# schemat1.net
KiCad netlist of a schematic drawn in EAGLE
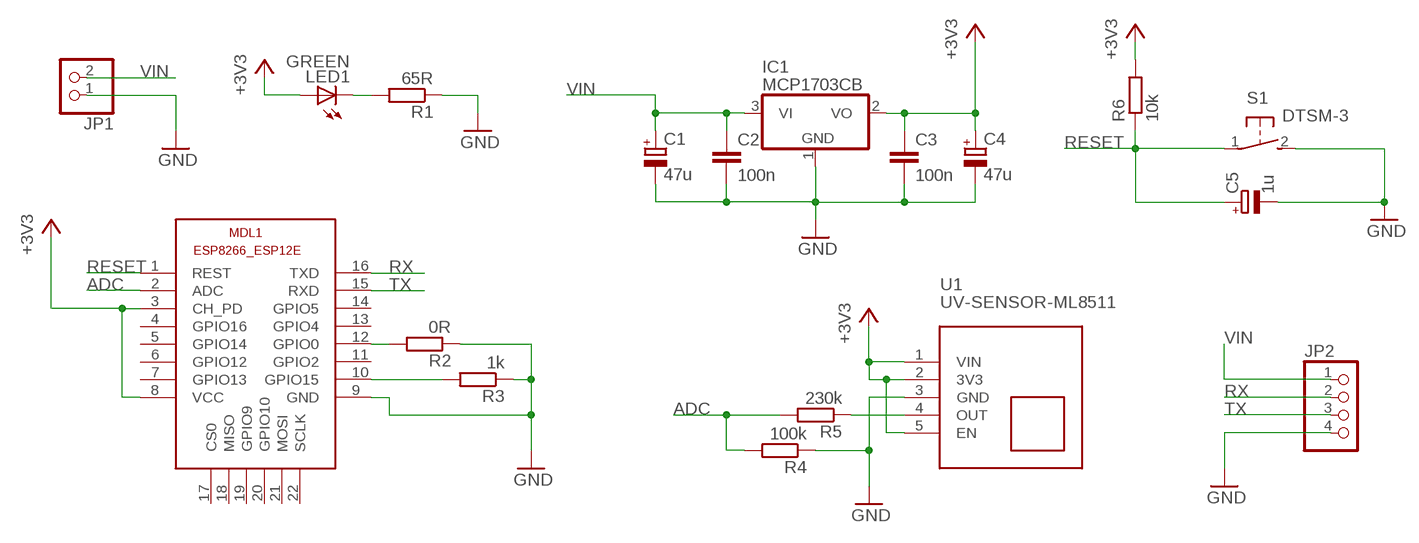
[diagram p0: schematic, sheet 1]

(export (version "E")
  (design (tool "Eeschema 10.0.6"))
  (components
    (comp (ref "C1")
      (value "47u")
      (footprint "eagle-import:CT3528")
      (libsource (lib "eagle-import") (part "CPOL-EUCT3528"))
    )
    (comp (ref "C2")
      (value "100n")
      (footprint "eagle-import:C0805")
      (libsource (lib "eagle-import") (part "C-EUC0805"))
    )
    (comp (ref "C3")
      (value "100n")
      (footprint "eagle-import:C0805")
      (libsource (lib "eagle-import") (part "C-EUC0805"))
    )
    (comp (ref "C4")
      (value "47u")
      (footprint "eagle-import:CT3528")
      (libsource (lib "eagle-import") (part "CPOL-EUCT3528"))
    )
    (comp (ref "C5")
      (value "1u")
      (footprint "eagle-import:CT3216")
      (libsource (lib "eagle-import") (part "CPOL-EUCT3216"))
    )
    (comp (ref "IC1")
      (value "MCP1703CB")
      (footprint "eagle-import:SOT23")
      (libsource (lib "eagle-import") (part "MCP1703CB"))
    )
    (comp (ref "JP1")
      (value "PINHD-1X2")
      (footprint "eagle-import:1X02")
      (libsource (lib "eagle-import") (part "PINHD-1X2"))
    )
    (comp (ref "JP2")
      (value "PINHD-1X4/90")
      (footprint "eagle-import:1X04_90")
      (libsource (lib "eagle-import") (part "PINHD-1X4/90"))
    )
    (comp (ref "LED1")
      (value "GREEN")
      (footprint "eagle-import:LED_1206")
      (libsource (lib "eagle-import") (part "LED_E"))
    )
    (comp (ref "MDL1")
      (value "ESP8266-12EESP8266-ESP12E")
      (footprint "eagle-import:ESP8266-ESP12E")
      (libsource (lib "eagle-import") (part "ESP8266-12EESP8266-ESP12E"))
    )
    (comp (ref "R1")
      (value "65R")
      (footprint "eagle-import:R0805")
      (libsource (lib "eagle-import") (part "R-EU_R0805"))
    )
    (comp (ref "R2")
      (value "0R")
      (footprint "eagle-import:R0805")
      (libsource (lib "eagle-import") (part "R-EU_R0805"))
    )
    (comp (ref "R3")
      (value "1k")
      (footprint "eagle-import:R0805")
      (libsource (lib "eagle-import") (part "R-EU_R0805"))
    )
    (comp (ref "R4")
      (value "100k")
      (footprint "eagle-import:R0805")
      (libsource (lib "eagle-import") (part "R-EU_R0805"))
    )
    (comp (ref "R5")
      (value "230k")
      (footprint "eagle-import:R0805")
      (libsource (lib "eagle-import") (part "R-EU_R0805"))
    )
    (comp (ref "R6")
      (value "10k")
      (footprint "eagle-import:R0805")
      (libsource (lib "eagle-import") (part "R-EU_R0805"))
    )
    (comp (ref "S1")
      (value "DTSM-3")
      (footprint "eagle-import:DTSM-3")
      (libsource (lib "eagle-import") (part "DTSM-3"))
    )
    (comp (ref "U1")
      (value "UV-SENSOR-ML8511")
      (footprint "eagle-import:UV-SENSOR-ML8511")
      (libsource (lib "eagle-import") (part "UV-SENSOR-ML8511"))
    )
  )
  (nets
    (net (code "1") (name "+3V3") (class "Default")
      (node (ref "C3") (pin "1") (pinfunction "1_1") (pintype "passive"))
      (node (ref "C4") (pin "+") (pinfunction "+_+") (pintype "passive"))
      (node (ref "IC1") (pin "2") (pinfunction "VO_2") (pintype "passive"))
      (node (ref "LED1") (pin "A") (pinfunction "A_A") (pintype "passive"))
      (node (ref "MDL1") (pin "3") (pinfunction "CH_PD_3") (pintype "bidirectional"))
      (node (ref "MDL1") (pin "8") (pinfunction "VCC_8") (pintype "bidirectional"))
      (node (ref "R6") (pin "2") (pinfunction "2_2") (pintype "passive"))
      (node (ref "U1") (pin "1") (pinfunction "VIN_1") (pintype "power_in"))
      (node (ref "U1") (pin "2") (pinfunction "3V3_2") (pintype "power_in"))
      (node (ref "U1") (pin "5") (pinfunction "EN_5") (pintype "bidirectional"))
    )
    (net (code "2") (name "/ADC") (class "Default")
      (node (ref "MDL1") (pin "2") (pinfunction "ADC_2") (pintype "bidirectional"))
      (node (ref "R4") (pin "2") (pinfunction "2_2") (pintype "passive"))
      (node (ref "R5") (pin "2") (pinfunction "2_2") (pintype "passive"))
    )
    (net (code "3") (name "/RESET") (class "Default")
      (node (ref "C5") (pin "+") (pinfunction "+_+") (pintype "passive"))
      (node (ref "MDL1") (pin "1") (pinfunction "REST_1") (pintype "bidirectional"))
      (node (ref "R6") (pin "1") (pinfunction "1_1") (pintype "passive"))
      (node (ref "S1") (pin "1") (pinfunction "1_1") (pintype "passive"))
    )
    (net (code "4") (name "/RX") (class "Default")
      (node (ref "JP2") (pin "2") (pinfunction "2_2") (pintype "passive"))
      (node (ref "MDL1") (pin "16") (pinfunction "TXD_16") (pintype "bidirectional"))
    )
    (net (code "5") (name "/TX") (class "Default")
      (node (ref "JP2") (pin "3") (pinfunction "3_3") (pintype "passive"))
      (node (ref "MDL1") (pin "15") (pinfunction "RXD_15") (pintype "bidirectional"))
    )
    (net (code "6") (name "/VIN") (class "Default")
      (node (ref "C1") (pin "+") (pinfunction "+_+") (pintype "passive"))
      (node (ref "C2") (pin "1") (pinfunction "1_1") (pintype "passive"))
      (node (ref "IC1") (pin "3") (pinfunction "VI_3") (pintype "input"))
      (node (ref "JP1") (pin "2") (pinfunction "2_2") (pintype "passive"))
      (node (ref "JP2") (pin "1") (pinfunction "1_1") (pintype "passive"))
    )
    (net (code "7") (name "GND") (class "Default")
      (node (ref "C1") (pin "-") (pinfunction "-_-") (pintype "passive"))
      (node (ref "C2") (pin "2") (pinfunction "2_2") (pintype "passive"))
      (node (ref "C3") (pin "2") (pinfunction "2_2") (pintype "passive"))
      (node (ref "C4") (pin "-") (pinfunction "-_-") (pintype "passive"))
      (node (ref "C5") (pin "-") (pinfunction "-_-") (pintype "passive"))
      (node (ref "IC1") (pin "1") (pinfunction "GND_1") (pintype "passive"))
      (node (ref "JP1") (pin "1") (pinfunction "1_1") (pintype "passive"))
      (node (ref "JP2") (pin "4") (pinfunction "4_4") (pintype "passive"))
      (node (ref "MDL1") (pin "9") (pinfunction "GND_9") (pintype "bidirectional"))
      (node (ref "R1") (pin "1") (pinfunction "1_1") (pintype "passive"))
      (node (ref "R2") (pin "1") (pinfunction "1_1") (pintype "passive"))
      (node (ref "R3") (pin "1") (pinfunction "1_1") (pintype "passive"))
      (node (ref "R4") (pin "1") (pinfunction "1_1") (pintype "passive"))
      (node (ref "S1") (pin "2") (pinfunction "2_2") (pintype "passive"))
      (node (ref "U1") (pin "3") (pinfunction "GND_3") (pintype "power_in"))
    )
    (net (code "8") (name "Net-(LED1-PadC)") (class "Default")
      (node (ref "LED1") (pin "C") (pinfunction "C_C") (pintype "passive"))
      (node (ref "R1") (pin "2") (pinfunction "2_2") (pintype "passive"))
    )
    (net (code "9") (name "Net-(MDL1-GPIO0)") (class "Default")
      (node (ref "MDL1") (pin "12") (pinfunction "GPIO0_12") (pintype "bidirectional"))
      (node (ref "R2") (pin "2") (pinfunction "2_2") (pintype "passive"))
    )
    (net (code "10") (name "Net-(MDL1-GPIO15)") (class "Default")
      (node (ref "MDL1") (pin "10") (pinfunction "GPIO15_10") (pintype "bidirectional"))
      (node (ref "R3") (pin "2") (pinfunction "2_2") (pintype "passive"))
    )
    (net (code "11") (name "Net-(U1-OUT)") (class "Default")
      (node (ref "R5") (pin "1") (pinfunction "1_1") (pintype "passive"))
      (node (ref "U1") (pin "4") (pinfunction "OUT_4") (pintype "bidirectional"))
    )
    (net (code "12") (name "unconnected-(MDL1-CS0-Pad17)") (class "Default")
      (node (ref "MDL1") (pin "17") (pinfunction "CS0_17") (pintype "bidirectional"))
    )
    (net (code "13") (name "unconnected-(MDL1-GPIO2-Pad11)") (class "Default")
      (node (ref "MDL1") (pin "11") (pinfunction "GPIO2_11") (pintype "bidirectional"))
    )
    (net (code "14") (name "unconnected-(MDL1-GPIO4-Pad13)") (class "Default")
      (node (ref "MDL1") (pin "13") (pinfunction "GPIO4_13") (pintype "bidirectional"))
    )
    (net (code "15") (name "unconnected-(MDL1-GPIO5-Pad14)") (class "Default")
      (node (ref "MDL1") (pin "14") (pinfunction "GPIO5_14") (pintype "bidirectional"))
    )
    (net (code "16") (name "unconnected-(MDL1-GPIO9-Pad19)") (class "Default")
      (node (ref "MDL1") (pin "19") (pinfunction "GPIO9_19") (pintype "bidirectional"))
    )
    (net (code "17") (name "unconnected-(MDL1-GPIO10-Pad20)") (class "Default")
      (node (ref "MDL1") (pin "20") (pinfunction "GPIO10_20") (pintype "bidirectional"))
    )
    (net (code "18") (name "unconnected-(MDL1-GPIO12-Pad6)") (class "Default")
      (node (ref "MDL1") (pin "6") (pinfunction "GPIO12_6") (pintype "bidirectional"))
    )
    (net (code "19") (name "unconnected-(MDL1-GPIO13-Pad7)") (class "Default")
      (node (ref "MDL1") (pin "7") (pinfunction "GPIO13_7") (pintype "bidirectional"))
    )
    (net (code "20") (name "unconnected-(MDL1-GPIO14-Pad5)") (class "Default")
      (node (ref "MDL1") (pin "5") (pinfunction "GPIO14_5") (pintype "bidirectional"))
    )
    (net (code "21") (name "unconnected-(MDL1-GPIO16-Pad4)") (class "Default")
      (node (ref "MDL1") (pin "4") (pinfunction "GPIO16_4") (pintype "bidirectional"))
    )
    (net (code "22") (name "unconnected-(MDL1-MISO-Pad18)") (class "Default")
      (node (ref "MDL1") (pin "18") (pinfunction "MISO_18") (pintype "bidirectional"))
    )
    (net (code "23") (name "unconnected-(MDL1-MOSI-Pad21)") (class "Default")
      (node (ref "MDL1") (pin "21") (pinfunction "MOSI_21") (pintype "bidirectional"))
    )
    (net (code "24") (name "unconnected-(MDL1-SCLK-Pad22)") (class "Default")
      (node (ref "MDL1") (pin "22") (pinfunction "SCLK_22") (pintype "bidirectional"))
    )
  )
)
